# LED.net
KiCad netlist of a schematic drawn in Altium Designer
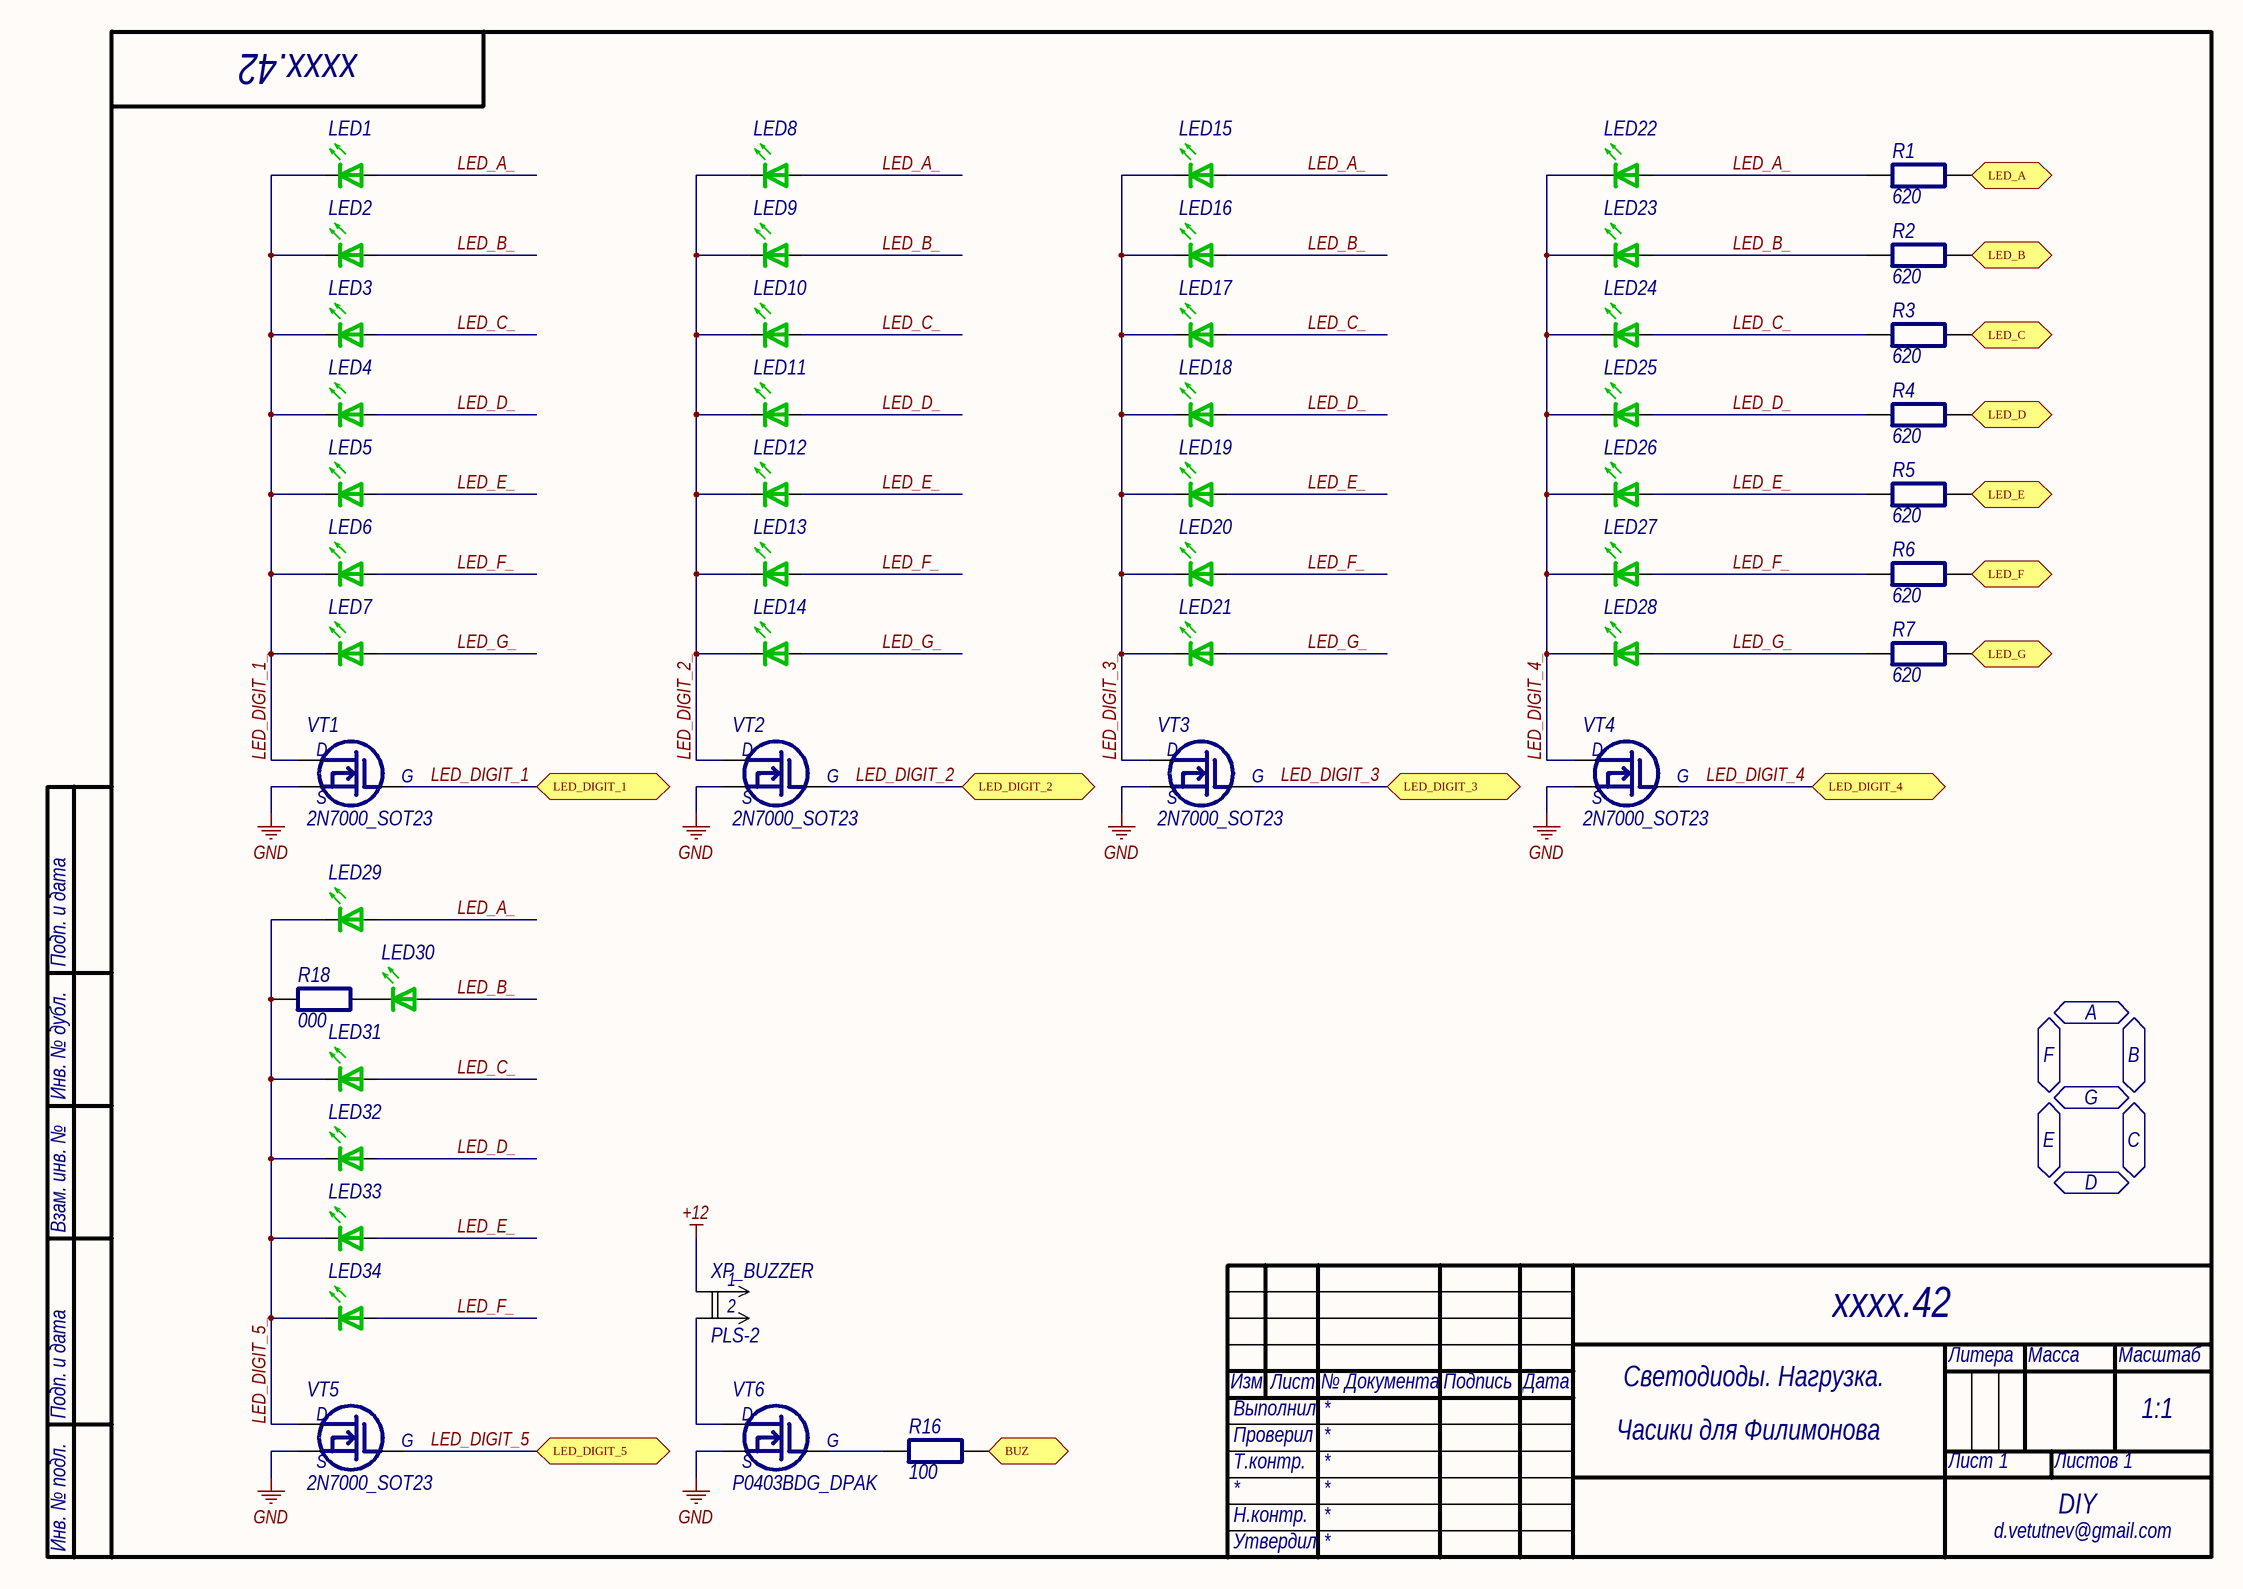
[diagram p0: LED.SchDoc]

(export (version "E")
  (design (tool "Eeschema 10.0.6"))
  (components
    (comp (ref "LED1")
      (value "Green 0805")
      (footprint "CD2012-0805 - Green")
      (libsource (lib "LED") (part "LED_Green_0805"))
    )
    (comp (ref "LED2")
      (value "Green 0805")
      (footprint "CD2012-0805 - Green")
      (libsource (lib "LED") (part "LED_Green_0805"))
    )
    (comp (ref "LED3")
      (value "Green 0805")
      (footprint "CD2012-0805 - Green")
      (libsource (lib "LED") (part "LED_Green_0805"))
    )
    (comp (ref "LED4")
      (value "Green 0805")
      (footprint "CD2012-0805 - Green")
      (libsource (lib "LED") (part "LED_Green_0805"))
    )
    (comp (ref "LED5")
      (value "Green 0805")
      (footprint "CD2012-0805 - Green")
      (libsource (lib "LED") (part "LED_Green_0805"))
    )
    (comp (ref "LED6")
      (value "Green 0805")
      (footprint "CD2012-0805 - Green")
      (libsource (lib "LED") (part "LED_Green_0805"))
    )
    (comp (ref "LED7")
      (value "Green 0805")
      (footprint "CD2012-0805 - Green")
      (libsource (lib "LED") (part "LED_Green_0805"))
    )
    (comp (ref "LED8")
      (value "Green 0805")
      (footprint "CD2012-0805 - Green")
      (libsource (lib "LED") (part "LED_Green_0805"))
    )
    (comp (ref "LED9")
      (value "Green 0805")
      (footprint "CD2012-0805 - Green")
      (libsource (lib "LED") (part "LED_Green_0805"))
    )
    (comp (ref "LED10")
      (value "Green 0805")
      (footprint "CD2012-0805 - Green")
      (libsource (lib "LED") (part "LED_Green_0805"))
    )
    (comp (ref "LED11")
      (value "Green 0805")
      (footprint "CD2012-0805 - Green")
      (libsource (lib "LED") (part "LED_Green_0805"))
    )
    (comp (ref "LED12")
      (value "Green 0805")
      (footprint "CD2012-0805 - Green")
      (libsource (lib "LED") (part "LED_Green_0805"))
    )
    (comp (ref "LED13")
      (value "Green 0805")
      (footprint "CD2012-0805 - Green")
      (libsource (lib "LED") (part "LED_Green_0805"))
    )
    (comp (ref "LED14")
      (value "Green 0805")
      (footprint "CD2012-0805 - Green")
      (libsource (lib "LED") (part "LED_Green_0805"))
    )
    (comp (ref "LED15")
      (value "Green 0805")
      (footprint "CD2012-0805 - Green")
      (libsource (lib "LED") (part "LED_Green_0805"))
    )
    (comp (ref "LED16")
      (value "Green 0805")
      (footprint "CD2012-0805 - Green")
      (libsource (lib "LED") (part "LED_Green_0805"))
    )
    (comp (ref "LED17")
      (value "Green 0805")
      (footprint "CD2012-0805 - Green")
      (libsource (lib "LED") (part "LED_Green_0805"))
    )
    (comp (ref "LED18")
      (value "Green 0805")
      (footprint "CD2012-0805 - Green")
      (libsource (lib "LED") (part "LED_Green_0805"))
    )
    (comp (ref "LED19")
      (value "Green 0805")
      (footprint "CD2012-0805 - Green")
      (libsource (lib "LED") (part "LED_Green_0805"))
    )
    (comp (ref "LED20")
      (value "Green 0805")
      (footprint "CD2012-0805 - Green")
      (libsource (lib "LED") (part "LED_Green_0805"))
    )
    (comp (ref "LED21")
      (value "Green 0805")
      (footprint "CD2012-0805 - Green")
      (libsource (lib "LED") (part "LED_Green_0805"))
    )
    (comp (ref "LED22")
      (value "Green 0805")
      (footprint "CD2012-0805 - Green")
      (libsource (lib "LED") (part "LED_Green_0805"))
    )
    (comp (ref "LED23")
      (value "Green 0805")
      (footprint "CD2012-0805 - Green")
      (libsource (lib "LED") (part "LED_Green_0805"))
    )
    (comp (ref "LED24")
      (value "Green 0805")
      (footprint "CD2012-0805 - Green")
      (libsource (lib "LED") (part "LED_Green_0805"))
    )
    (comp (ref "LED25")
      (value "Green 0805")
      (footprint "CD2012-0805 - Green")
      (libsource (lib "LED") (part "LED_Green_0805"))
    )
    (comp (ref "LED26")
      (value "Green 0805")
      (footprint "CD2012-0805 - Green")
      (libsource (lib "LED") (part "LED_Green_0805"))
    )
    (comp (ref "LED27")
      (value "Green 0805")
      (footprint "CD2012-0805 - Green")
      (libsource (lib "LED") (part "LED_Green_0805"))
    )
    (comp (ref "LED28")
      (value "Green 0805")
      (footprint "CD2012-0805 - Green")
      (libsource (lib "LED") (part "LED_Green_0805"))
    )
    (comp (ref "LED29")
      (value "Green 0805")
      (footprint "CD2012-0805 - Green")
      (libsource (lib "LED") (part "LED_Green_0805"))
    )
    (comp (ref "LED30")
      (value "Green 0805")
      (footprint "CD2012-0805 - Green")
      (libsource (lib "LED") (part "LED_Green_0805"))
    )
    (comp (ref "LED31")
      (value "Green 0805")
      (footprint "CD2012-0805 - Green")
      (libsource (lib "LED") (part "LED_Green_0805"))
    )
    (comp (ref "LED32")
      (value "Green 0805")
      (footprint "CD2012-0805 - Green")
      (libsource (lib "LED") (part "LED_Green_0805"))
    )
    (comp (ref "LED33")
      (value "Green 0805")
      (footprint "CD2012-0805 - Green")
      (libsource (lib "LED") (part "LED_Green_0805"))
    )
    (comp (ref "LED34")
      (value "Green 0805")
      (footprint "CD2012-0805 - Green")
      (libsource (lib "LED") (part "LED_Green_0805"))
    )
    (comp (ref "R1")
      (value "620")
      (footprint "RESC2012M")
      (fields (field (name "PARTNUMBER") "SMD 0805"))
      (libsource (lib "Resistors") (part "Res_0805"))
    )
    (comp (ref "R2")
      (value "620")
      (footprint "RESC2012M")
      (fields (field (name "PARTNUMBER") "SMD 0805"))
      (libsource (lib "Resistors") (part "Res_0805"))
    )
    (comp (ref "R3")
      (value "620")
      (footprint "RESC2012M")
      (fields (field (name "PARTNUMBER") "SMD 0805"))
      (libsource (lib "Resistors") (part "Res_0805"))
    )
    (comp (ref "R4")
      (value "620")
      (footprint "RESC2012M")
      (fields (field (name "PARTNUMBER") "SMD 0805"))
      (libsource (lib "Resistors") (part "Res_0805"))
    )
    (comp (ref "R5")
      (value "620")
      (footprint "RESC2012M")
      (fields (field (name "PARTNUMBER") "SMD 0805"))
      (libsource (lib "Resistors") (part "Res_0805"))
    )
    (comp (ref "R6")
      (value "620")
      (footprint "RESC2012M")
      (fields (field (name "PARTNUMBER") "SMD 0805"))
      (libsource (lib "Resistors") (part "Res_0805"))
    )
    (comp (ref "R7")
      (value "620")
      (footprint "RESC2012M")
      (fields (field (name "PARTNUMBER") "SMD 0805"))
      (libsource (lib "Resistors") (part "Res_0805"))
    )
    (comp (ref "R16")
      (value "100")
      (footprint "RESC2012M")
      (fields (field (name "PARTNUMBER") "SMD 0805"))
      (libsource (lib "Resistors") (part "Res_0805"))
    )
    (comp (ref "R18")
      (value "000")
      (footprint "RESC3216M")
      (fields (field (name "PARTNUMBER") "SMD 1206"))
      (libsource (lib "Resistors") (part "Res_1206"))
    )
    (comp (ref "VT1")
      (value "2N7000_SOT23")
      (footprint "SOT23")
      (libsource (lib "MOSFET") (part "2N7000_SOT23"))
    )
    (comp (ref "VT2")
      (value "2N7000_SOT23")
      (footprint "SOT23")
      (libsource (lib "MOSFET") (part "2N7000_SOT23"))
    )
    (comp (ref "VT3")
      (value "2N7000_SOT23")
      (footprint "SOT23")
      (libsource (lib "MOSFET") (part "2N7000_SOT23"))
    )
    (comp (ref "VT4")
      (value "2N7000_SOT23")
      (footprint "SOT23")
      (libsource (lib "MOSFET") (part "2N7000_SOT23"))
    )
    (comp (ref "VT5")
      (value "2N7000_SOT23")
      (footprint "SOT23")
      (libsource (lib "MOSFET") (part "2N7000_SOT23"))
    )
    (comp (ref "VT6")
      (value "P0403BDG_DPAK")
      (footprint "DPAK(TO252)")
      (libsource (lib "MOSFET") (part "P0403BDG_DPAK"))
    )
    (comp (ref "XP_BUZZER")
      (value "PLS-2")
      (footprint "PLS-2")
      (libsource (lib "Connectors PLS 2.54mm") (part "PLS-2"))
    )
  )
  (nets
    (net (code "1") (name "+12") (class "Default")
      (node (ref "XP_BUZZER") (pin "1") (pinfunction "1_1") (pintype "passive"))
    )
    (net (code "2") (name "/BUZ") (class "Default")
      (node (ref "R16") (pin "2") (pinfunction "2_2") (pintype "passive"))
    )
    (net (code "3") (name "/LED_A") (class "Default")
      (node (ref "R1") (pin "2") (pinfunction "2_2") (pintype "passive"))
    )
    (net (code "4") (name "/LED_A_") (class "Default")
      (node (ref "LED1") (pin "1") (pinfunction "1_1") (pintype "passive"))
      (node (ref "LED15") (pin "1") (pinfunction "1_1") (pintype "passive"))
      (node (ref "LED22") (pin "1") (pinfunction "1_1") (pintype "passive"))
      (node (ref "LED29") (pin "1") (pinfunction "1_1") (pintype "passive"))
      (node (ref "LED8") (pin "1") (pinfunction "1_1") (pintype "passive"))
      (node (ref "R1") (pin "1") (pinfunction "1_1") (pintype "passive"))
    )
    (net (code "5") (name "/LED_B") (class "Default")
      (node (ref "R2") (pin "2") (pinfunction "2_2") (pintype "passive"))
    )
    (net (code "6") (name "/LED_B_") (class "Default")
      (node (ref "LED16") (pin "1") (pinfunction "1_1") (pintype "passive"))
      (node (ref "LED2") (pin "1") (pinfunction "1_1") (pintype "passive"))
      (node (ref "LED23") (pin "1") (pinfunction "1_1") (pintype "passive"))
      (node (ref "LED30") (pin "1") (pinfunction "1_1") (pintype "passive"))
      (node (ref "LED9") (pin "1") (pinfunction "1_1") (pintype "passive"))
      (node (ref "R2") (pin "1") (pinfunction "1_1") (pintype "passive"))
    )
    (net (code "7") (name "/LED_C") (class "Default")
      (node (ref "R3") (pin "2") (pinfunction "2_2") (pintype "passive"))
    )
    (net (code "8") (name "/LED_C_") (class "Default")
      (node (ref "LED10") (pin "1") (pinfunction "1_1") (pintype "passive"))
      (node (ref "LED17") (pin "1") (pinfunction "1_1") (pintype "passive"))
      (node (ref "LED24") (pin "1") (pinfunction "1_1") (pintype "passive"))
      (node (ref "LED3") (pin "1") (pinfunction "1_1") (pintype "passive"))
      (node (ref "LED31") (pin "1") (pinfunction "1_1") (pintype "passive"))
      (node (ref "R3") (pin "1") (pinfunction "1_1") (pintype "passive"))
    )
    (net (code "9") (name "/LED_D") (class "Default")
      (node (ref "R4") (pin "2") (pinfunction "2_2") (pintype "passive"))
    )
    (net (code "10") (name "/LED_DIGIT_1") (class "Default")
      (node (ref "VT1") (pin "1") (pinfunction "G_1") (pintype "power_in"))
    )
    (net (code "11") (name "/LED_DIGIT_1_") (class "Default")
      (node (ref "LED1") (pin "2") (pinfunction "2_2") (pintype "passive"))
      (node (ref "LED2") (pin "2") (pinfunction "2_2") (pintype "passive"))
      (node (ref "LED3") (pin "2") (pinfunction "2_2") (pintype "passive"))
      (node (ref "LED4") (pin "2") (pinfunction "2_2") (pintype "passive"))
      (node (ref "LED5") (pin "2") (pinfunction "2_2") (pintype "passive"))
      (node (ref "LED6") (pin "2") (pinfunction "2_2") (pintype "passive"))
      (node (ref "LED7") (pin "2") (pinfunction "2_2") (pintype "passive"))
      (node (ref "VT1") (pin "3") (pinfunction "D_3") (pintype "power_in"))
    )
    (net (code "12") (name "/LED_DIGIT_2") (class "Default")
      (node (ref "VT2") (pin "1") (pinfunction "G_1") (pintype "power_in"))
    )
    (net (code "13") (name "/LED_DIGIT_2_") (class "Default")
      (node (ref "LED10") (pin "2") (pinfunction "2_2") (pintype "passive"))
      (node (ref "LED11") (pin "2") (pinfunction "2_2") (pintype "passive"))
      (node (ref "LED12") (pin "2") (pinfunction "2_2") (pintype "passive"))
      (node (ref "LED13") (pin "2") (pinfunction "2_2") (pintype "passive"))
      (node (ref "LED14") (pin "2") (pinfunction "2_2") (pintype "passive"))
      (node (ref "LED8") (pin "2") (pinfunction "2_2") (pintype "passive"))
      (node (ref "LED9") (pin "2") (pinfunction "2_2") (pintype "passive"))
      (node (ref "VT2") (pin "3") (pinfunction "D_3") (pintype "power_in"))
    )
    (net (code "14") (name "/LED_DIGIT_3") (class "Default")
      (node (ref "VT3") (pin "1") (pinfunction "G_1") (pintype "power_in"))
    )
    (net (code "15") (name "/LED_DIGIT_3_") (class "Default")
      (node (ref "LED15") (pin "2") (pinfunction "2_2") (pintype "passive"))
      (node (ref "LED16") (pin "2") (pinfunction "2_2") (pintype "passive"))
      (node (ref "LED17") (pin "2") (pinfunction "2_2") (pintype "passive"))
      (node (ref "LED18") (pin "2") (pinfunction "2_2") (pintype "passive"))
      (node (ref "LED19") (pin "2") (pinfunction "2_2") (pintype "passive"))
      (node (ref "LED20") (pin "2") (pinfunction "2_2") (pintype "passive"))
      (node (ref "LED21") (pin "2") (pinfunction "2_2") (pintype "passive"))
      (node (ref "VT3") (pin "3") (pinfunction "D_3") (pintype "power_in"))
    )
    (net (code "16") (name "/LED_DIGIT_4") (class "Default")
      (node (ref "VT4") (pin "1") (pinfunction "G_1") (pintype "power_in"))
    )
    (net (code "17") (name "/LED_DIGIT_4_") (class "Default")
      (node (ref "LED22") (pin "2") (pinfunction "2_2") (pintype "passive"))
      (node (ref "LED23") (pin "2") (pinfunction "2_2") (pintype "passive"))
      (node (ref "LED24") (pin "2") (pinfunction "2_2") (pintype "passive"))
      (node (ref "LED25") (pin "2") (pinfunction "2_2") (pintype "passive"))
      (node (ref "LED26") (pin "2") (pinfunction "2_2") (pintype "passive"))
      (node (ref "LED27") (pin "2") (pinfunction "2_2") (pintype "passive"))
      (node (ref "LED28") (pin "2") (pinfunction "2_2") (pintype "passive"))
      (node (ref "VT4") (pin "3") (pinfunction "D_3") (pintype "power_in"))
    )
    (net (code "18") (name "/LED_DIGIT_5") (class "Default")
      (node (ref "VT5") (pin "1") (pinfunction "G_1") (pintype "power_in"))
    )
    (net (code "19") (name "/LED_DIGIT_5_") (class "Default")
      (node (ref "LED29") (pin "2") (pinfunction "2_2") (pintype "passive"))
      (node (ref "LED31") (pin "2") (pinfunction "2_2") (pintype "passive"))
      (node (ref "LED32") (pin "2") (pinfunction "2_2") (pintype "passive"))
      (node (ref "LED33") (pin "2") (pinfunction "2_2") (pintype "passive"))
      (node (ref "LED34") (pin "2") (pinfunction "2_2") (pintype "passive"))
      (node (ref "R18") (pin "1") (pinfunction "1_1") (pintype "passive"))
      (node (ref "VT5") (pin "3") (pinfunction "D_3") (pintype "power_in"))
    )
    (net (code "20") (name "/LED_D_") (class "Default")
      (node (ref "LED11") (pin "1") (pinfunction "1_1") (pintype "passive"))
      (node (ref "LED18") (pin "1") (pinfunction "1_1") (pintype "passive"))
      (node (ref "LED25") (pin "1") (pinfunction "1_1") (pintype "passive"))
      (node (ref "LED32") (pin "1") (pinfunction "1_1") (pintype "passive"))
      (node (ref "LED4") (pin "1") (pinfunction "1_1") (pintype "passive"))
      (node (ref "R4") (pin "1") (pinfunction "1_1") (pintype "passive"))
    )
    (net (code "21") (name "/LED_E") (class "Default")
      (node (ref "R5") (pin "2") (pinfunction "2_2") (pintype "passive"))
    )
    (net (code "22") (name "/LED_E_") (class "Default")
      (node (ref "LED12") (pin "1") (pinfunction "1_1") (pintype "passive"))
      (node (ref "LED19") (pin "1") (pinfunction "1_1") (pintype "passive"))
      (node (ref "LED26") (pin "1") (pinfunction "1_1") (pintype "passive"))
      (node (ref "LED33") (pin "1") (pinfunction "1_1") (pintype "passive"))
      (node (ref "LED5") (pin "1") (pinfunction "1_1") (pintype "passive"))
      (node (ref "R5") (pin "1") (pinfunction "1_1") (pintype "passive"))
    )
    (net (code "23") (name "/LED_F") (class "Default")
      (node (ref "R6") (pin "2") (pinfunction "2_2") (pintype "passive"))
    )
    (net (code "24") (name "/LED_F_") (class "Default")
      (node (ref "LED13") (pin "1") (pinfunction "1_1") (pintype "passive"))
      (node (ref "LED20") (pin "1") (pinfunction "1_1") (pintype "passive"))
      (node (ref "LED27") (pin "1") (pinfunction "1_1") (pintype "passive"))
      (node (ref "LED34") (pin "1") (pinfunction "1_1") (pintype "passive"))
      (node (ref "LED6") (pin "1") (pinfunction "1_1") (pintype "passive"))
      (node (ref "R6") (pin "1") (pinfunction "1_1") (pintype "passive"))
    )
    (net (code "25") (name "/LED_G") (class "Default")
      (node (ref "R7") (pin "2") (pinfunction "2_2") (pintype "passive"))
    )
    (net (code "26") (name "/LED_G_") (class "Default")
      (node (ref "LED14") (pin "1") (pinfunction "1_1") (pintype "passive"))
      (node (ref "LED21") (pin "1") (pinfunction "1_1") (pintype "passive"))
      (node (ref "LED28") (pin "1") (pinfunction "1_1") (pintype "passive"))
      (node (ref "LED7") (pin "1") (pinfunction "1_1") (pintype "passive"))
      (node (ref "R7") (pin "1") (pinfunction "1_1") (pintype "passive"))
    )
    (net (code "27") (name "GND") (class "Default")
      (node (ref "VT1") (pin "2") (pinfunction "S_2") (pintype "power_in"))
      (node (ref "VT2") (pin "2") (pinfunction "S_2") (pintype "power_in"))
      (node (ref "VT3") (pin "2") (pinfunction "S_2") (pintype "power_in"))
      (node (ref "VT4") (pin "2") (pinfunction "S_2") (pintype "power_in"))
      (node (ref "VT5") (pin "2") (pinfunction "S_2") (pintype "power_in"))
      (node (ref "VT6") (pin "3") (pinfunction "S_3") (pintype "power_in"))
    )
    (net (code "28") (name "Net-(LED30-Pad2)") (class "Default")
      (node (ref "LED30") (pin "2") (pinfunction "2_2") (pintype "passive"))
      (node (ref "R18") (pin "2") (pinfunction "2_2") (pintype "passive"))
    )
    (net (code "29") (name "Net-(VT6-D)") (class "Default")
      (node (ref "VT6") (pin "4") (pinfunction "D_4") (pintype "power_in"))
      (node (ref "XP_BUZZER") (pin "2") (pinfunction "2_2") (pintype "passive"))
    )
    (net (code "30") (name "Net-(VT6-G)") (class "Default")
      (node (ref "R16") (pin "1") (pinfunction "1_1") (pintype "passive"))
      (node (ref "VT6") (pin "1") (pinfunction "G_1") (pintype "power_in"))
    )
  )
)
